# LT1054_LinierRegurator.net
KiCad netlist of a schematic drawn in EAGLE
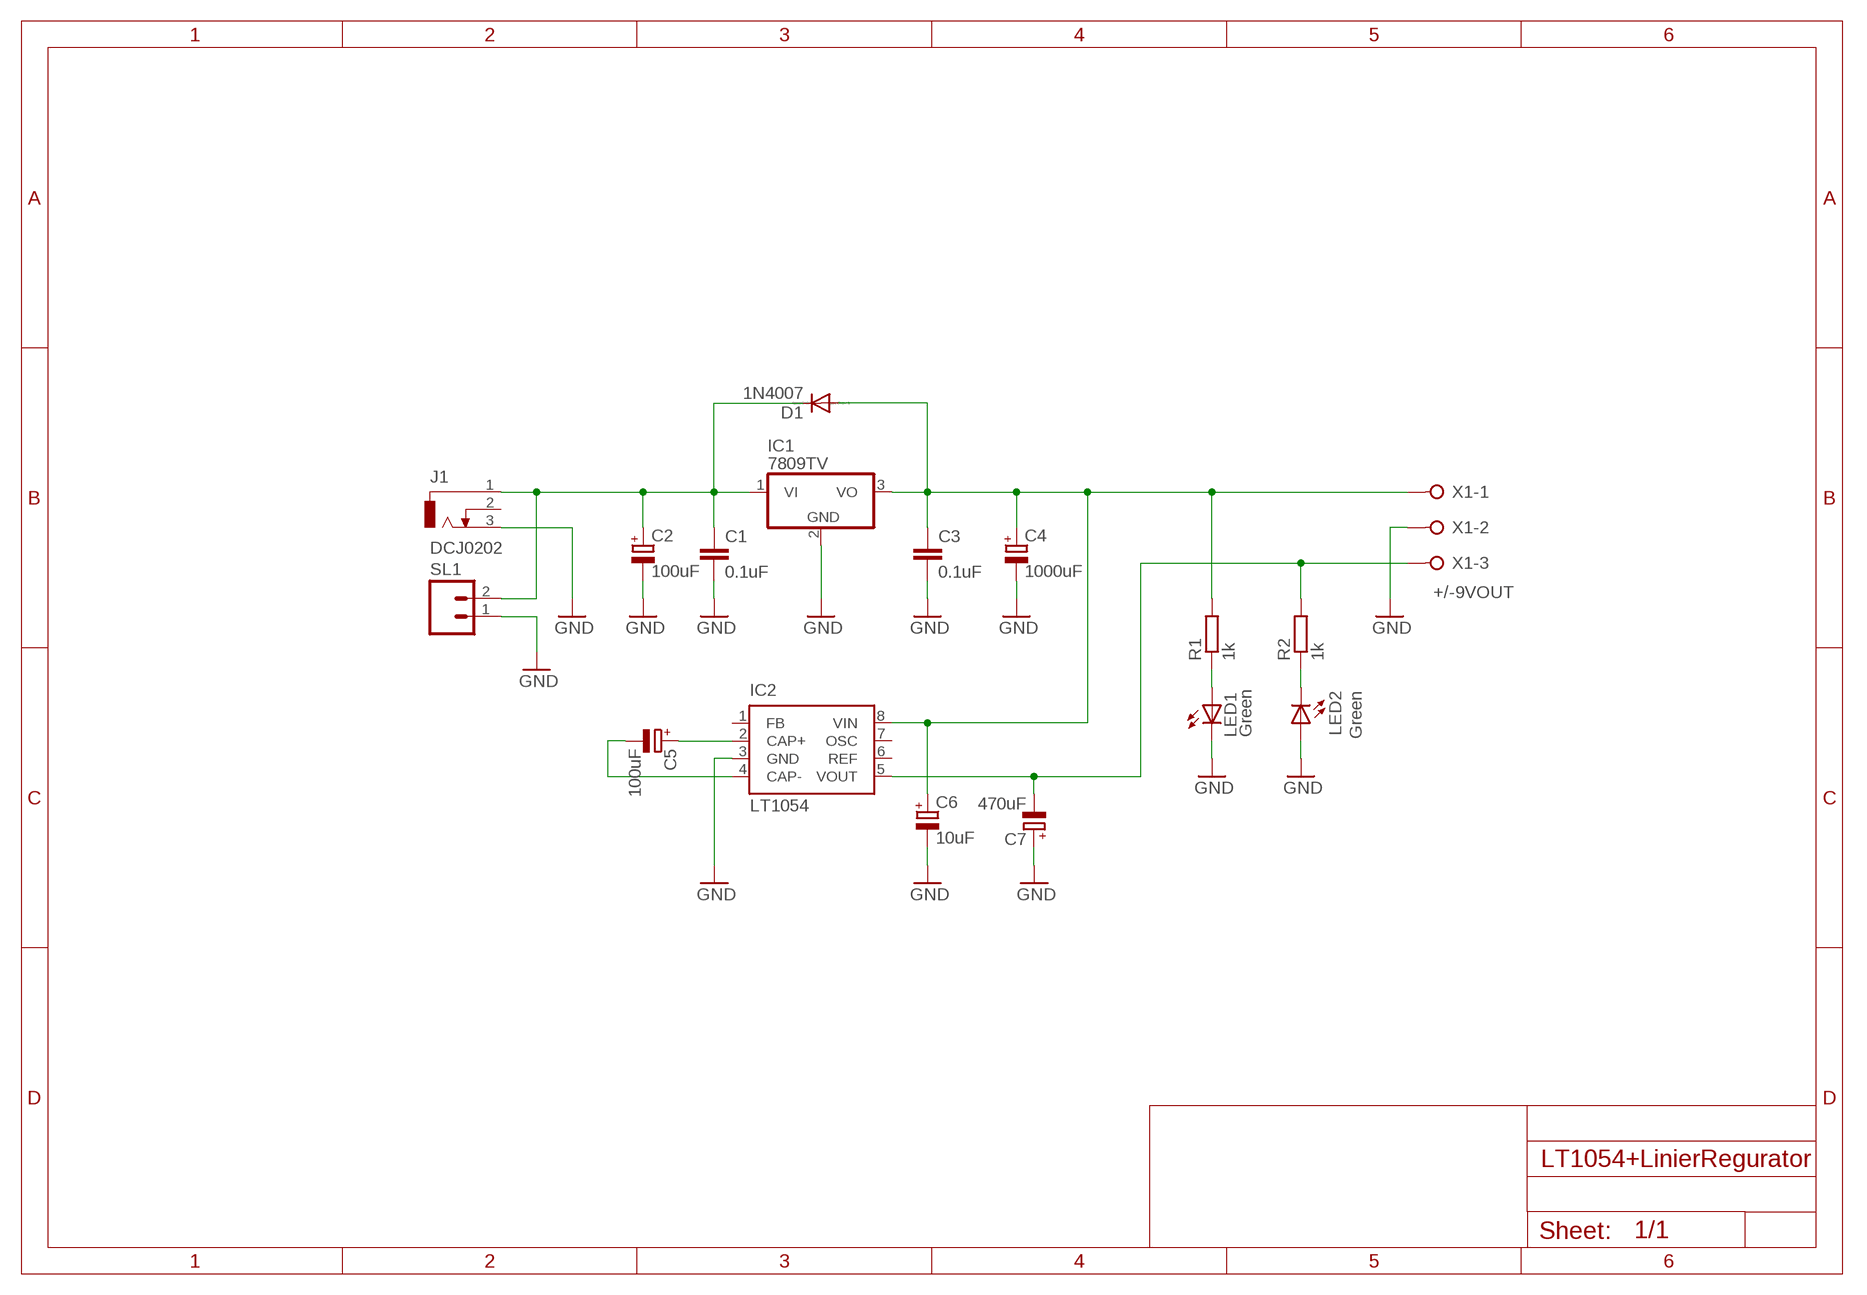
[diagram p0: schematic, sheet 1]

(export (version "E")
  (design (tool "Eeschema 10.0.6"))
  (components
    (comp (ref "C1")
      (value "0.1uF")
      (footprint "eagle-import:C025-024X044")
      (libsource (lib "eagle-import") (part "C-EU025-024X044"))
    )
    (comp (ref "C2")
      (value "100uF")
      (footprint "eagle-import:E2,5-7")
      (libsource (lib "eagle-import") (part "CPOL-EUE2.5-7"))
    )
    (comp (ref "C3")
      (value "0.1uF")
      (footprint "eagle-import:C025-024X044")
      (libsource (lib "eagle-import") (part "C-EU025-024X044"))
    )
    (comp (ref "C4")
      (value "1000uF")
      (footprint "eagle-import:E5-13")
      (libsource (lib "eagle-import") (part "CPOL-EUE5-13"))
    )
    (comp (ref "C5")
      (value "100uF")
      (footprint "eagle-import:E2,5-7")
      (libsource (lib "eagle-import") (part "CPOL-EUE2.5-7"))
    )
    (comp (ref "C6")
      (value "10uF")
      (footprint "eagle-import:E2,5-5")
      (libsource (lib "eagle-import") (part "CPOL-EUE2.5-5"))
    )
    (comp (ref "C7")
      (value "470uF")
      (footprint "eagle-import:E5-8,5")
      (libsource (lib "eagle-import") (part "CPOL-EUE5-8.5"))
    )
    (comp (ref "D1")
      (value "1N4007")
      (footprint "eagle-import:DO41-10")
      (libsource (lib "eagle-import") (part "1N4004"))
    )
    (comp (ref "IC1")
      (value "7809TV")
      (footprint "eagle-import:TO220V")
      (libsource (lib "eagle-import") (part "78TV05"))
    )
    (comp (ref "IC2")
      (value "LT1054")
      (footprint "eagle-import:DIL8")
      (libsource (lib "eagle-import") (part "LT1054"))
    )
    (comp (ref "J1")
      (value "DCJ0202")
      (footprint "eagle-import:DCJ0202")
      (libsource (lib "eagle-import") (part "DCJ0202"))
    )
    (comp (ref "LED1")
      (value "Green")
      (footprint "eagle-import:LED3MM")
      (libsource (lib "eagle-import") (part "LED3MM"))
    )
    (comp (ref "LED2")
      (value "Green")
      (footprint "eagle-import:LED3MM")
      (libsource (lib "eagle-import") (part "LED3MM"))
    )
    (comp (ref "R1")
      (value "1k")
      (footprint "eagle-import:0207_7")
      (libsource (lib "eagle-import") (part "R-EU_0207/7"))
    )
    (comp (ref "R2")
      (value "1k")
      (footprint "eagle-import:0207_7")
      (libsource (lib "eagle-import") (part "R-EU_0207/7"))
    )
    (comp (ref "SL1")
      (value "M02")
      (footprint "eagle-import:02P")
      (libsource (lib "eagle-import") (part "M02"))
    )
    (comp (ref "X1")
      (value "+/-9VOUT")
      (footprint "eagle-import:W237-3E")
      (libsource (lib "eagle-import") (part "W237-3E"))
    )
  )
  (nets
    (net (code "1") (name "GND") (class "Default")
      (node (ref "C1") (pin "2") (pinfunction "2_2") (pintype "passive"))
      (node (ref "C2") (pin "-") (pinfunction "-_-") (pintype "passive"))
      (node (ref "C3") (pin "2") (pinfunction "2_2") (pintype "passive"))
      (node (ref "C4") (pin "-") (pinfunction "-_-") (pintype "passive"))
      (node (ref "C6") (pin "-") (pinfunction "-_-") (pintype "passive"))
      (node (ref "C7") (pin "+") (pinfunction "+_+") (pintype "passive"))
      (node (ref "IC1") (pin "2") (pinfunction "GND_2") (pintype "passive"))
      (node (ref "IC2") (pin "3") (pinfunction "GND_3") (pintype "power_in"))
      (node (ref "J1") (pin "3") (pinfunction "3_3") (pintype "passive"))
      (node (ref "LED1") (pin "K") (pinfunction "C_K") (pintype "passive"))
      (node (ref "LED2") (pin "A") (pinfunction "A_A") (pintype "passive"))
      (node (ref "SL1") (pin "1") (pinfunction "1_1") (pintype "passive"))
      (node (ref "X1") (pin "2") (pinfunction "KL_2") (pintype "passive"))
    )
    (net (code "2") (name "Net-(IC1-VI)") (class "Default")
      (node (ref "C1") (pin "1") (pinfunction "1_1") (pintype "passive"))
      (node (ref "C2") (pin "+") (pinfunction "+_+") (pintype "passive"))
      (node (ref "D1") (pin "C") (pinfunction "C_C") (pintype "passive"))
      (node (ref "IC1") (pin "1") (pinfunction "VI_1") (pintype "input"))
      (node (ref "J1") (pin "1") (pinfunction "1_1") (pintype "passive"))
      (node (ref "SL1") (pin "2") (pinfunction "2_2") (pintype "passive"))
    )
    (net (code "3") (name "Net-(IC1-VO)") (class "Default")
      (node (ref "C3") (pin "1") (pinfunction "1_1") (pintype "passive"))
      (node (ref "C4") (pin "+") (pinfunction "+_+") (pintype "passive"))
      (node (ref "C6") (pin "+") (pinfunction "+_+") (pintype "passive"))
      (node (ref "D1") (pin "A") (pinfunction "A_A") (pintype "passive"))
      (node (ref "IC1") (pin "3") (pinfunction "VO_3") (pintype "passive"))
      (node (ref "IC2") (pin "8") (pinfunction "VIN_8") (pintype "input"))
      (node (ref "R1") (pin "2") (pinfunction "2_2") (pintype "passive"))
      (node (ref "X1") (pin "1") (pinfunction "KL_1") (pintype "passive"))
    )
    (net (code "4") (name "Net-(IC2-CAP+)") (class "Default")
      (node (ref "C5") (pin "+") (pinfunction "+_+") (pintype "passive"))
      (node (ref "IC2") (pin "2") (pinfunction "CAP+_2") (pintype "passive"))
    )
    (net (code "5") (name "Net-(IC2-CAP-)") (class "Default")
      (node (ref "C5") (pin "-") (pinfunction "-_-") (pintype "passive"))
      (node (ref "IC2") (pin "4") (pinfunction "CAP-_4") (pintype "passive"))
    )
    (net (code "6") (name "Net-(IC2-VOUT)") (class "Default")
      (node (ref "C7") (pin "-") (pinfunction "-_-") (pintype "passive"))
      (node (ref "IC2") (pin "5") (pinfunction "VOUT_5") (pintype "output"))
      (node (ref "R2") (pin "2") (pinfunction "2_2") (pintype "passive"))
      (node (ref "X1") (pin "3") (pinfunction "KL_3") (pintype "passive"))
    )
    (net (code "7") (name "Net-(LED1-PadA)") (class "Default")
      (node (ref "LED1") (pin "A") (pinfunction "A_A") (pintype "passive"))
      (node (ref "R1") (pin "1") (pinfunction "1_1") (pintype "passive"))
    )
    (net (code "8") (name "Net-(LED2-C)") (class "Default")
      (node (ref "LED2") (pin "K") (pinfunction "C_K") (pintype "passive"))
      (node (ref "R2") (pin "1") (pinfunction "1_1") (pintype "passive"))
    )
    (net (code "9") (name "unconnected-(IC2-FB-Pad1)") (class "Default")
      (node (ref "IC2") (pin "1") (pinfunction "FB_1") (pintype "input"))
    )
    (net (code "10") (name "unconnected-(IC2-OSC-Pad7)") (class "Default")
      (node (ref "IC2") (pin "7") (pinfunction "OSC_7") (pintype "output"))
    )
    (net (code "11") (name "unconnected-(IC2-REF-Pad6)") (class "Default")
      (node (ref "IC2") (pin "6") (pinfunction "REF_6") (pintype "input"))
    )
    (net (code "12") (name "unconnected-(J1-Pad2)") (class "Default")
      (node (ref "J1") (pin "2") (pinfunction "2_2") (pintype "passive"))
    )
  )
)
